# VF_24Euro_PCB.net
KiCad netlist of a schematic drawn in EAGLE
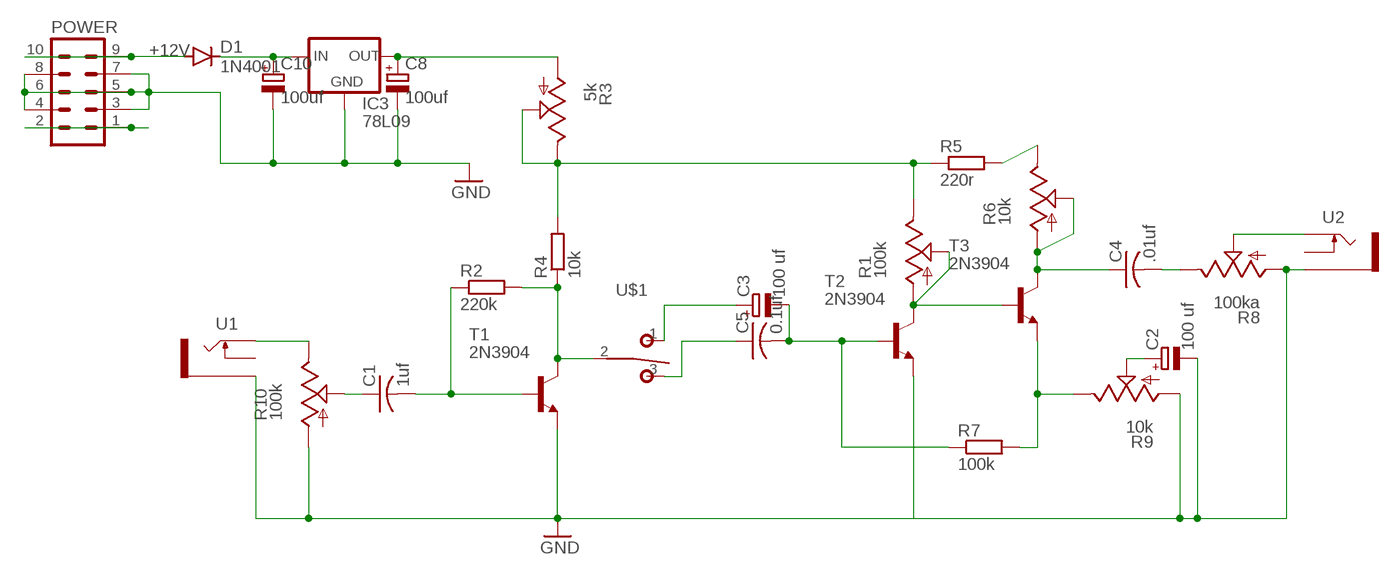
[diagram p0: schematic, sheet 1]

(export (version "E")
  (design (tool "Eeschema 10.0.6"))
  (components
    (comp (ref "C1")
      (value "1uf")
      (footprint "eagle-import:C050-025X075")
      (libsource (lib "eagle-import") (part "C-US050-025X075"))
    )
    (comp (ref "C2")
      (value "100 uf")
      (footprint "eagle-import:E2,5-7")
      (libsource (lib "eagle-import") (part "CPOL-EUE2.5-7"))
    )
    (comp (ref "C3")
      (value "100 uf")
      (footprint "eagle-import:E2,5-7")
      (libsource (lib "eagle-import") (part "CPOL-EUE2.5-7"))
    )
    (comp (ref "C4")
      (value ".01uf")
      (footprint "eagle-import:C050-025X075")
      (libsource (lib "eagle-import") (part "C-US050-025X075"))
    )
    (comp (ref "C5")
      (value "0.1uf")
      (footprint "eagle-import:C050-025X075")
      (libsource (lib "eagle-import") (part "C-US050-025X075"))
    )
    (comp (ref "C8")
      (value "100uf")
      (footprint "eagle-import:E2,5-7")
      (libsource (lib "eagle-import") (part "CPOL-EUE2.5-7"))
    )
    (comp (ref "C10")
      (value "100uf")
      (footprint "eagle-import:E2,5-7")
      (libsource (lib "eagle-import") (part "CPOL-EUE2.5-7"))
    )
    (comp (ref "D1")
      (value "1N4001")
      (footprint "eagle-import:DO41-10")
      (libsource (lib "eagle-import") (part "1N4004"))
    )
    (comp (ref "IC3")
      (value "78L09")
      (footprint "eagle-import:78LXX")
      (libsource (lib "eagle-import") (part "78LXX"))
    )
    (comp (ref "POWER")
      (value "10_PIN_HEADER")
      (footprint "eagle-import:MA05-2")
      (libsource (lib "eagle-import") (part "10_PIN_HEADER"))
    )
    (comp (ref "R1")
      (value "100k")
      (footprint "eagle-import:9MM_SNAP-IN_POT")
      (libsource (lib "eagle-import") (part "9MM_SNAP-IN_POT_"))
    )
    (comp (ref "R2")
      (value "220k")
      (footprint "eagle-import:7MM_RESISTOR")
      (libsource (lib "eagle-import") (part "RESISTOR7MM"))
    )
    (comp (ref "R3")
      (value "5k")
      (footprint "eagle-import:9MM_SNAP-IN_POT")
      (libsource (lib "eagle-import") (part "9MM_SNAP-IN_POT_"))
    )
    (comp (ref "R4")
      (value "10k")
      (footprint "eagle-import:7MM_RESISTOR")
      (libsource (lib "eagle-import") (part "RESISTOR7MM"))
    )
    (comp (ref "R5")
      (value "220r")
      (footprint "eagle-import:7MM_RESISTOR")
      (libsource (lib "eagle-import") (part "RESISTOR7MM"))
    )
    (comp (ref "R6")
      (value "10k")
      (footprint "eagle-import:9MM_SNAP-IN_POT")
      (libsource (lib "eagle-import") (part "9MM_SNAP-IN_POT_"))
    )
    (comp (ref "R7")
      (value "100k")
      (footprint "eagle-import:7MM_RESISTOR")
      (libsource (lib "eagle-import") (part "RESISTOR7MM"))
    )
    (comp (ref "R8")
      (value "100ka")
      (footprint "eagle-import:9MM_SNAP-IN_POT")
      (libsource (lib "eagle-import") (part "9MM_SNAP-IN_POT_"))
    )
    (comp (ref "R9")
      (value "10k")
      (footprint "eagle-import:9MM_SNAP-IN_POT")
      (libsource (lib "eagle-import") (part "9MM_SNAP-IN_POT_"))
    )
    (comp (ref "R10")
      (value "100k")
      (footprint "eagle-import:9MM_SNAP-IN_POT")
      (libsource (lib "eagle-import") (part "9MM_SNAP-IN_POT_"))
    )
    (comp (ref "T1")
      (value "2N3904")
      (footprint "eagle-import:TO92")
      (libsource (lib "eagle-import") (part "2N3904"))
    )
    (comp (ref "T2")
      (value "2N3904")
      (footprint "eagle-import:TO92")
      (libsource (lib "eagle-import") (part "2N3904"))
    )
    (comp (ref "T3")
      (value "2N3904")
      (footprint "eagle-import:TO92")
      (libsource (lib "eagle-import") (part "2N3904"))
    )
    (comp (ref "U$1")
      (value "T-80-T-SPDT-ON-OFF-ON")
      (footprint "eagle-import:M9040P")
      (libsource (lib "eagle-import") (part "T-80-T-SPDT-ON-OFF-ON"))
    )
    (comp (ref "U1")
      (value "THONKICONNNEW")
      (footprint "eagle-import:WQP-PJ301M-12_JACK")
      (libsource (lib "eagle-import") (part "THONKICONNNEW"))
    )
    (comp (ref "U2")
      (value "THONKICONNNEW")
      (footprint "eagle-import:WQP-PJ301M-12_JACK")
      (libsource (lib "eagle-import") (part "THONKICONNNEW"))
    )
  )
  (nets
    (net (code "1") (name "/+12V") (class "Default")
      (node (ref "C10") (pin "+") (pinfunction "+_+") (pintype "passive"))
      (node (ref "D1") (pin "C") (pinfunction "C_C") (pintype "passive"))
      (node (ref "IC3") (pin "IN") (pinfunction "IN_IN") (pintype "input"))
    )
    (net (code "2") (name "GND") (class "Default")
      (node (ref "C10") (pin "-") (pinfunction "-_-") (pintype "passive"))
      (node (ref "C2") (pin "-") (pinfunction "-_-") (pintype "passive"))
      (node (ref "C8") (pin "-") (pinfunction "-_-") (pintype "passive"))
      (node (ref "IC3") (pin "GND") (pinfunction "GND_GND") (pintype "input"))
      (node (ref "POWER") (pin "3") (pinfunction "3_3") (pintype "passive"))
      (node (ref "POWER") (pin "4") (pinfunction "4_4") (pintype "passive"))
      (node (ref "POWER") (pin "5") (pinfunction "5_5") (pintype "passive"))
      (node (ref "POWER") (pin "6") (pinfunction "6_6") (pintype "passive"))
      (node (ref "POWER") (pin "7") (pinfunction "7_7") (pintype "passive"))
      (node (ref "POWER") (pin "8") (pinfunction "8_8") (pintype "passive"))
      (node (ref "R10") (pin "1") (pinfunction "A_1") (pintype "passive"))
      (node (ref "R8") (pin "1") (pinfunction "A_1") (pintype "passive"))
      (node (ref "R9") (pin "1") (pinfunction "A_1") (pintype "passive"))
      (node (ref "T1") (pin "3") (pinfunction "E_3") (pintype "passive"))
      (node (ref "T2") (pin "3") (pinfunction "E_3") (pintype "passive"))
      (node (ref "U1") (pin "P$3_SLEEVE") (pinfunction "SLEEVE_P$3_SLEEVE") (pintype "passive"))
      (node (ref "U2") (pin "P$3_SLEEVE") (pinfunction "SLEEVE_P$3_SLEEVE") (pintype "passive"))
    )
    (net (code "3") (name "Net-(D1-PadA)") (class "Default")
      (node (ref "D1") (pin "A") (pinfunction "A_A") (pintype "passive"))
      (node (ref "POWER") (pin "10") (pinfunction "10_10") (pintype "passive"))
      (node (ref "POWER") (pin "9") (pinfunction "9_9") (pintype "passive"))
    )
    (net (code "4") (name "Net-(POWER-Pad1)") (class "Default")
      (node (ref "POWER") (pin "1") (pinfunction "1_1") (pintype "passive"))
      (node (ref "POWER") (pin "2") (pinfunction "2_2") (pintype "passive"))
    )
    (net (code "5") (name "Net-(R1-A)") (class "Default")
      (node (ref "R1") (pin "1") (pinfunction "A_1") (pintype "passive"))
      (node (ref "R1") (pin "2") (pinfunction "S_2") (pintype "passive"))
      (node (ref "T2") (pin "1") (pinfunction "C_1") (pintype "passive"))
      (node (ref "T3") (pin "2") (pinfunction "B_2") (pintype "passive"))
    )
    (net (code "6") (name "Net-(R1-E)") (class "Default")
      (node (ref "R1") (pin "3") (pinfunction "E_3") (pintype "passive"))
      (node (ref "R3") (pin "2") (pinfunction "S_2") (pintype "passive"))
      (node (ref "R3") (pin "3") (pinfunction "E_3") (pintype "passive"))
      (node (ref "R4") (pin "2") (pinfunction "2_2") (pintype "passive"))
      (node (ref "R5") (pin "1") (pinfunction "1_1") (pintype "passive"))
    )
    (net (code "7") (name "Net-(R3-A)") (class "Default")
      (node (ref "C8") (pin "+") (pinfunction "+_+") (pintype "passive"))
      (node (ref "IC3") (pin "OUT") (pinfunction "OUT_OUT") (pintype "passive"))
      (node (ref "R3") (pin "1") (pinfunction "A_1") (pintype "passive"))
    )
    (net (code "8") (name "Net-(R6-A)") (class "Default")
      (node (ref "C4") (pin "1") (pinfunction "1_1") (pintype "passive"))
      (node (ref "R6") (pin "1") (pinfunction "A_1") (pintype "passive"))
      (node (ref "R6") (pin "2") (pinfunction "S_2") (pintype "passive"))
      (node (ref "T3") (pin "1") (pinfunction "C_1") (pintype "passive"))
    )
    (net (code "9") (name "Net-(R6-E)") (class "Default")
      (node (ref "R5") (pin "2") (pinfunction "2_2") (pintype "passive"))
      (node (ref "R6") (pin "3") (pinfunction "E_3") (pintype "passive"))
    )
    (net (code "10") (name "Net-(R8-E)") (class "Default")
      (node (ref "C4") (pin "2") (pinfunction "2_2") (pintype "passive"))
      (node (ref "R8") (pin "3") (pinfunction "E_3") (pintype "passive"))
    )
    (net (code "11") (name "Net-(R8-S)") (class "Default")
      (node (ref "R8") (pin "2") (pinfunction "S_2") (pintype "passive"))
      (node (ref "U2") (pin "P$1_TIP") (pinfunction "TIP_P$1_TIP") (pintype "passive"))
    )
    (net (code "12") (name "Net-(R9-E)") (class "Default")
      (node (ref "R7") (pin "2") (pinfunction "2_2") (pintype "passive"))
      (node (ref "R9") (pin "3") (pinfunction "E_3") (pintype "passive"))
      (node (ref "T3") (pin "3") (pinfunction "E_3") (pintype "passive"))
    )
    (net (code "13") (name "Net-(R9-S)") (class "Default")
      (node (ref "C2") (pin "+") (pinfunction "+_+") (pintype "passive"))
      (node (ref "R9") (pin "2") (pinfunction "S_2") (pintype "passive"))
    )
    (net (code "14") (name "Net-(R10-E)") (class "Default")
      (node (ref "R10") (pin "3") (pinfunction "E_3") (pintype "passive"))
      (node (ref "U1") (pin "P$1_TIP") (pinfunction "TIP_P$1_TIP") (pintype "passive"))
    )
    (net (code "15") (name "Net-(R10-S)") (class "Default")
      (node (ref "C1") (pin "1") (pinfunction "1_1") (pintype "passive"))
      (node (ref "R10") (pin "2") (pinfunction "S_2") (pintype "passive"))
    )
    (net (code "16") (name "Net-(T1-B)") (class "Default")
      (node (ref "C1") (pin "2") (pinfunction "2_2") (pintype "passive"))
      (node (ref "R2") (pin "1") (pinfunction "1_1") (pintype "passive"))
      (node (ref "T1") (pin "2") (pinfunction "B_2") (pintype "passive"))
    )
    (net (code "17") (name "Net-(T1-C)") (class "Default")
      (node (ref "R2") (pin "2") (pinfunction "2_2") (pintype "passive"))
      (node (ref "R4") (pin "1") (pinfunction "1_1") (pintype "passive"))
      (node (ref "T1") (pin "1") (pinfunction "C_1") (pintype "passive"))
      (node (ref "U$1") (pin "2") (pinfunction "P_2") (pintype "passive"))
    )
    (net (code "18") (name "Net-(T2-B)") (class "Default")
      (node (ref "C3") (pin "-") (pinfunction "-_-") (pintype "passive"))
      (node (ref "C5") (pin "2") (pinfunction "2_2") (pintype "passive"))
      (node (ref "R7") (pin "1") (pinfunction "1_1") (pintype "passive"))
      (node (ref "T2") (pin "2") (pinfunction "B_2") (pintype "passive"))
    )
    (net (code "19") (name "Net-(U$1-O)") (class "Default")
      (node (ref "C3") (pin "+") (pinfunction "+_+") (pintype "passive"))
      (node (ref "U$1") (pin "1") (pinfunction "O_1") (pintype "passive"))
    )
    (net (code "20") (name "Net-(U$1-S)") (class "Default")
      (node (ref "C5") (pin "1") (pinfunction "1_1") (pintype "passive"))
      (node (ref "U$1") (pin "3") (pinfunction "S_3") (pintype "passive"))
    )
    (net (code "21") (name "unconnected-(U1-SWITCH-PadP$2_SWITCH)") (class "Default")
      (node (ref "U1") (pin "P$2_SWITCH") (pinfunction "SWITCH_P$2_SWITCH") (pintype "passive"))
    )
    (net (code "22") (name "unconnected-(U2-SWITCH-PadP$2_SWITCH)") (class "Default")
      (node (ref "U2") (pin "P$2_SWITCH") (pinfunction "SWITCH_P$2_SWITCH") (pintype "passive"))
    )
  )
)
